# VMA.net
KiCad netlist of a schematic drawn in Altium Designer
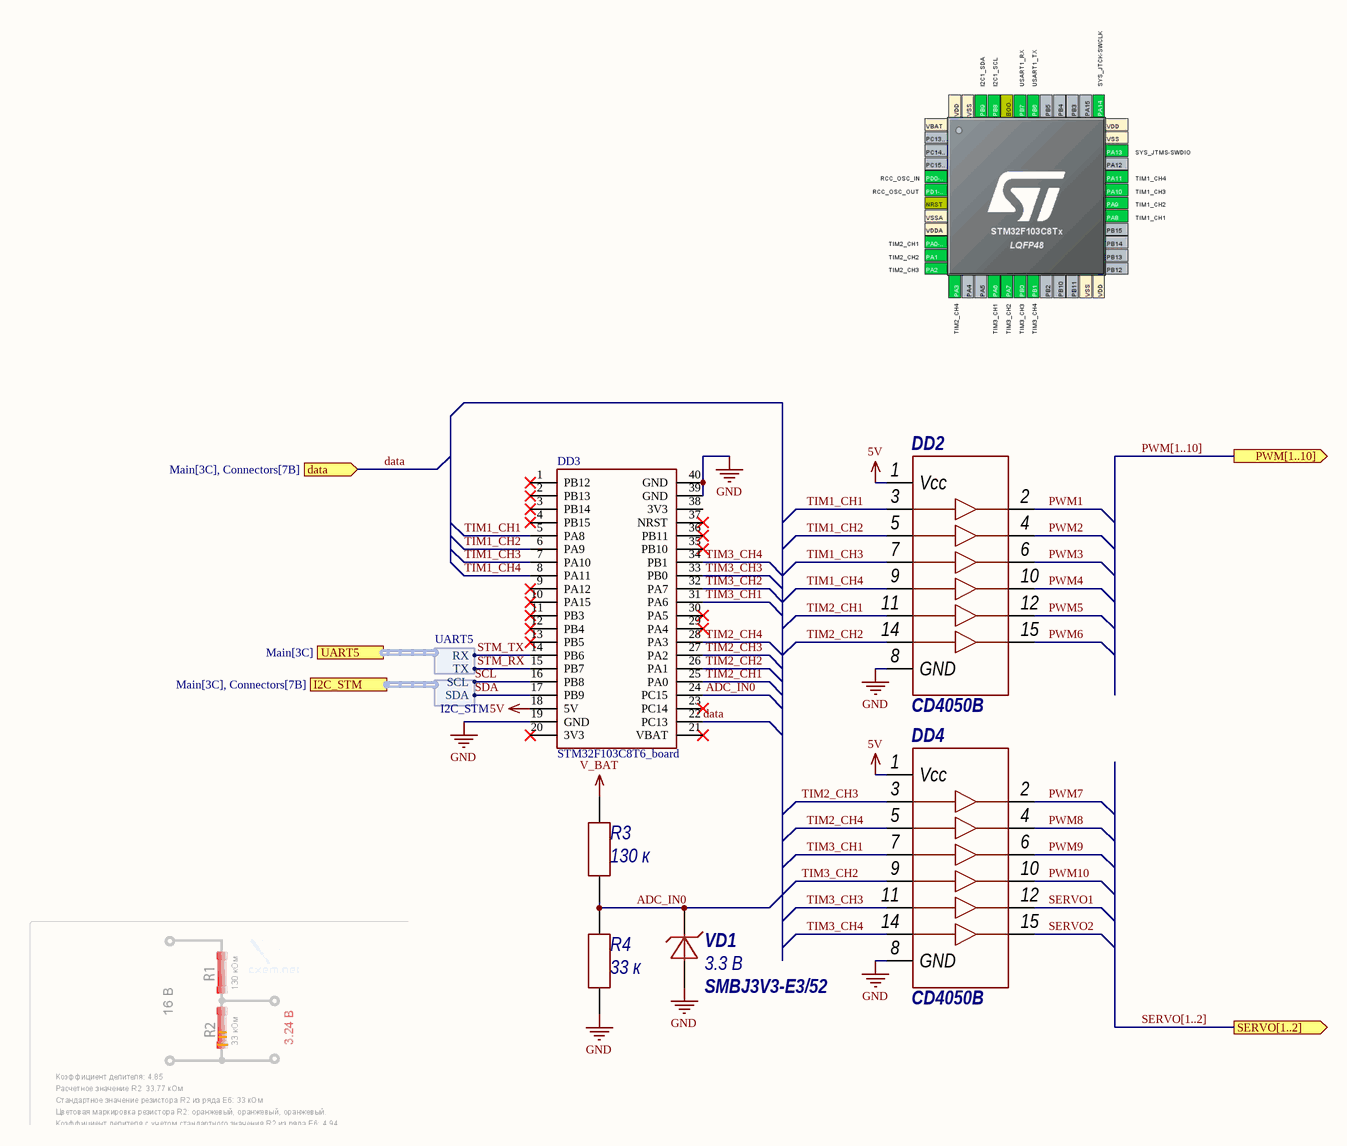
[diagram p0: VMA.SchDoc]

(export (version "E")
  (design (tool "Eeschema 10.0.6"))
  (components
    (comp (ref "DD2")
      (value "CD4050B")
      (footprint "DIP16_in_socket")
      (description "Шесть буферных элементов")
      (libsource (lib "Hydrolib") (part "CD4050B"))
    )
    (comp (ref "DD3")
      (value "STM32F103C8T6_board")
      (footprint "STM32F103C8T6_board")
      (description "blue pill")
      (libsource (lib "Hydrolib") (part "STM32F103C8T6_board"))
    )
    (comp (ref "DD4")
      (value "CD4050B")
      (footprint "DIP16_in_socket")
      (description "Шесть буферных элементов")
      (libsource (lib "Hydrolib") (part "CD4050B"))
    )
    (comp (ref "R3")
      (value "130 к")
      (footprint "0603R")
      (description "Резистор номиналом 130 кОм и точностью 1%")
      (fields (field (name "PART NUMBER") "Resistor_130k_1_0603") (field (name "TOLERANCE") "1%"))
      (libsource (lib "Hydrolib") (part "Resistor"))
    )
    (comp (ref "R4")
      (value "33 к")
      (footprint "0603R")
      (description "Резистор номиналом 33 кОм и точностью 1%")
      (fields (field (name "PART NUMBER") "Resistor_33k_1_0603") (field (name "TOLERANCE") "1%"))
      (libsource (lib "Hydrolib") (part "Resistor"))
    )
    (comp (ref "VD1")
      (value "SMBJ3V3-E3/52")
      (footprint "SMB")
      (description "Защитный диод на 15 В, рассеиваемая мощность 600 Вт")
      (fields (field (name "ALTIUM_VALUE") "3.3 В") (field (name "PART NUMBER") "SMBJ15A"))
      (libsource (lib "Hydrolib") (part "TVS_1_1dir"))
    )
  )
  (nets
    (net (code "4") (name "/ADC_IN0") (class "Default")
      (node (ref "DD3") (pin "24") (pinfunction "PC15_24") (pintype "passive"))
      (node (ref "R3") (pin "1") (pinfunction "1_1") (pintype "passive"))
      (node (ref "R4") (pin "2") (pinfunction "2_2") (pintype "passive"))
      (node (ref "VD1") (pin "2") (pinfunction "2_2") (pintype "passive"))
    )
    (net (code "5") (name "/PWM1") (class "Default")
      (node (ref "DD2") (pin "2") (pinfunction "Y1_2") (pintype "passive"))
    )
    (net (code "6") (name "/PWM2") (class "Default")
      (node (ref "DD2") (pin "4") (pinfunction "Y2_4") (pintype "passive"))
    )
    (net (code "7") (name "/PWM3") (class "Default")
      (node (ref "DD2") (pin "6") (pinfunction "Y3_6") (pintype "passive"))
    )
    (net (code "8") (name "/PWM4") (class "Default")
      (node (ref "DD2") (pin "10") (pinfunction "Y10_10") (pintype "passive"))
    )
    (net (code "9") (name "/PWM5") (class "Default")
      (node (ref "DD2") (pin "12") (pinfunction "Y5_12") (pintype "passive"))
    )
    (net (code "10") (name "/PWM6") (class "Default")
      (node (ref "DD2") (pin "15") (pinfunction "Y6_15") (pintype "passive"))
    )
    (net (code "11") (name "/PWM7") (class "Default")
      (node (ref "DD4") (pin "2") (pinfunction "Y1_2") (pintype "passive"))
    )
    (net (code "12") (name "/PWM8") (class "Default")
      (node (ref "DD4") (pin "4") (pinfunction "Y2_4") (pintype "passive"))
    )
    (net (code "13") (name "/PWM9") (class "Default")
      (node (ref "DD4") (pin "6") (pinfunction "Y3_6") (pintype "passive"))
    )
    (net (code "14") (name "/PWM10") (class "Default")
      (node (ref "DD4") (pin "10") (pinfunction "Y10_10") (pintype "passive"))
    )
    (net (code "16") (name "/SDA") (class "Default")
      (node (ref "DD3") (pin "17") (pinfunction "PB9_17") (pintype "passive"))
    )
    (net (code "17") (name "/SERVO1") (class "Default")
      (node (ref "DD4") (pin "12") (pinfunction "Y5_12") (pintype "passive"))
    )
    (net (code "18") (name "/SERVO2") (class "Default")
      (node (ref "DD4") (pin "15") (pinfunction "Y6_15") (pintype "passive"))
    )
    (net (code "20") (name "/STM_RX") (class "Default")
      (node (ref "DD3") (pin "15") (pinfunction "PB7_15") (pintype "passive"))
    )
    (net (code "21") (name "/STM_TX") (class "Default")
      (node (ref "DD3") (pin "14") (pinfunction "PB6_14") (pintype "passive"))
    )
    (net (code "22") (name "/TIM1_CH1") (class "Default")
      (node (ref "DD2") (pin "3") (pinfunction "A1_3") (pintype "passive"))
      (node (ref "DD3") (pin "5") (pinfunction "PA8_5") (pintype "passive"))
    )
    (net (code "23") (name "/TIM1_CH2") (class "Default")
      (node (ref "DD2") (pin "5") (pinfunction "A2_5") (pintype "passive"))
      (node (ref "DD3") (pin "6") (pinfunction "PA9_6") (pintype "passive"))
    )
    (net (code "24") (name "/TIM1_CH3") (class "Default")
      (node (ref "DD2") (pin "7") (pinfunction "A3_7") (pintype "passive"))
      (node (ref "DD3") (pin "7") (pinfunction "PA10_7") (pintype "passive"))
    )
    (net (code "25") (name "/TIM1_CH4") (class "Default")
      (node (ref "DD2") (pin "9") (pinfunction "A4_9") (pintype "passive"))
      (node (ref "DD3") (pin "8") (pinfunction "PA11_8") (pintype "passive"))
    )
    (net (code "26") (name "/TIM2_CH1") (class "Default")
      (node (ref "DD2") (pin "11") (pinfunction "A5_11") (pintype "passive"))
      (node (ref "DD3") (pin "25") (pinfunction "PA0_25") (pintype "passive"))
    )
    (net (code "27") (name "/TIM2_CH2") (class "Default")
      (node (ref "DD2") (pin "14") (pinfunction "A6_14") (pintype "passive"))
      (node (ref "DD3") (pin "26") (pinfunction "PA1_26") (pintype "passive"))
    )
    (net (code "28") (name "/TIM2_CH3") (class "Default")
      (node (ref "DD3") (pin "27") (pinfunction "PA2_27") (pintype "passive"))
      (node (ref "DD4") (pin "3") (pinfunction "A1_3") (pintype "passive"))
    )
    (net (code "29") (name "/TIM2_CH4") (class "Default")
      (node (ref "DD3") (pin "28") (pinfunction "PA3_28") (pintype "passive"))
      (node (ref "DD4") (pin "5") (pinfunction "A2_5") (pintype "passive"))
    )
    (net (code "30") (name "/TIM3_CH1") (class "Default")
      (node (ref "DD3") (pin "31") (pinfunction "PA6_31") (pintype "passive"))
      (node (ref "DD4") (pin "7") (pinfunction "A3_7") (pintype "passive"))
    )
    (net (code "31") (name "/TIM3_CH2") (class "Default")
      (node (ref "DD3") (pin "32") (pinfunction "PA7_32") (pintype "passive"))
      (node (ref "DD4") (pin "9") (pinfunction "A4_9") (pintype "passive"))
    )
    (net (code "32") (name "/TIM3_CH3") (class "Default")
      (node (ref "DD3") (pin "33") (pinfunction "PB0_33") (pintype "passive"))
      (node (ref "DD4") (pin "11") (pinfunction "A5_11") (pintype "passive"))
    )
    (net (code "33") (name "/TIM3_CH4") (class "Default")
      (node (ref "DD3") (pin "34") (pinfunction "PB1_34") (pintype "passive"))
      (node (ref "DD4") (pin "14") (pinfunction "A6_14") (pintype "passive"))
    )
    (net (code "35") (name "/data") (class "Default")
      (node (ref "DD3") (pin "22") (pinfunction "PC13_22") (pintype "passive"))
    )
    (net (code "37") (name "/{SCL}") (class "Default")
      (node (ref "DD3") (pin "16") (pinfunction "PB8_16") (pintype "passive"))
    )
    (net (code "38") (name "5V") (class "Default")
      (node (ref "DD2") (pin "1") (pinfunction "Vcc_1") (pintype "passive"))
      (node (ref "DD3") (pin "18") (pinfunction "5V_18") (pintype "passive"))
      (node (ref "DD4") (pin "1") (pinfunction "Vcc_1") (pintype "passive"))
    )
    (net (code "39") (name "GND") (class "Default")
      (node (ref "DD2") (pin "8") (pinfunction "GND_8") (pintype "passive"))
      (node (ref "DD3") (pin "19") (pinfunction "GND_19") (pintype "passive"))
      (node (ref "DD3") (pin "39") (pinfunction "GND_39") (pintype "passive"))
      (node (ref "DD3") (pin "40") (pinfunction "GND_40") (pintype "passive"))
      (node (ref "DD4") (pin "8") (pinfunction "GND_8") (pintype "passive"))
      (node (ref "R4") (pin "1") (pinfunction "1_1") (pintype "passive"))
      (node (ref "VD1") (pin "1") (pinfunction "1_1") (pintype "passive"))
    )
    (net (code "40") (name "V_BAT") (class "Default")
      (node (ref "R3") (pin "2") (pinfunction "2_2") (pintype "passive"))
    )
    (net (code "41") (name "unconnected-(DD3-3V3-Pad20)") (class "Default")
      (node (ref "DD3") (pin "20") (pinfunction "3V3_20") (pintype "passive+no_connect"))
    )
    (net (code "42") (name "unconnected-(DD3-3V3-Pad38)") (class "Default")
      (node (ref "DD3") (pin "38") (pinfunction "3V3_38") (pintype "passive"))
    )
    (net (code "43") (name "unconnected-(DD3-NRST-Pad37)") (class "Default")
      (node (ref "DD3") (pin "37") (pinfunction "NRST_37") (pintype "passive+no_connect"))
    )
    (net (code "44") (name "unconnected-(DD3-PA4-Pad29)") (class "Default")
      (node (ref "DD3") (pin "29") (pinfunction "PA4_29") (pintype "passive+no_connect"))
    )
    (net (code "45") (name "unconnected-(DD3-PA5-Pad30)") (class "Default")
      (node (ref "DD3") (pin "30") (pinfunction "PA5_30") (pintype "passive+no_connect"))
    )
    (net (code "46") (name "unconnected-(DD3-PA12-Pad9)") (class "Default")
      (node (ref "DD3") (pin "9") (pinfunction "PA12_9") (pintype "passive+no_connect"))
    )
    (net (code "47") (name "unconnected-(DD3-PA15-Pad10)") (class "Default")
      (node (ref "DD3") (pin "10") (pinfunction "PA15_10") (pintype "passive+no_connect"))
    )
    (net (code "48") (name "unconnected-(DD3-PB3-Pad11)") (class "Default")
      (node (ref "DD3") (pin "11") (pinfunction "PB3_11") (pintype "passive+no_connect"))
    )
    (net (code "49") (name "unconnected-(DD3-PB4-Pad12)") (class "Default")
      (node (ref "DD3") (pin "12") (pinfunction "PB4_12") (pintype "passive+no_connect"))
    )
    (net (code "50") (name "unconnected-(DD3-PB5-Pad13)") (class "Default")
      (node (ref "DD3") (pin "13") (pinfunction "PB5_13") (pintype "passive+no_connect"))
    )
    (net (code "51") (name "unconnected-(DD3-PB10-Pad35)") (class "Default")
      (node (ref "DD3") (pin "35") (pinfunction "PB10_35") (pintype "passive+no_connect"))
    )
    (net (code "52") (name "unconnected-(DD3-PB11-Pad36)") (class "Default")
      (node (ref "DD3") (pin "36") (pinfunction "PB11_36") (pintype "passive+no_connect"))
    )
    (net (code "53") (name "unconnected-(DD3-PB12-Pad1)") (class "Default")
      (node (ref "DD3") (pin "1") (pinfunction "PB12_1") (pintype "passive+no_connect"))
    )
    (net (code "54") (name "unconnected-(DD3-PB13-Pad2)") (class "Default")
      (node (ref "DD3") (pin "2") (pinfunction "PB13_2") (pintype "passive+no_connect"))
    )
    (net (code "55") (name "unconnected-(DD3-PB14-Pad3)") (class "Default")
      (node (ref "DD3") (pin "3") (pinfunction "PB14_3") (pintype "passive+no_connect"))
    )
    (net (code "56") (name "unconnected-(DD3-PB15-Pad4)") (class "Default")
      (node (ref "DD3") (pin "4") (pinfunction "PB15_4") (pintype "passive+no_connect"))
    )
    (net (code "57") (name "unconnected-(DD3-PC14-Pad23)") (class "Default")
      (node (ref "DD3") (pin "23") (pinfunction "PC14_23") (pintype "passive+no_connect"))
    )
    (net (code "58") (name "unconnected-(DD3-VBAT-Pad21)") (class "Default")
      (node (ref "DD3") (pin "21") (pinfunction "VBAT_21") (pintype "passive+no_connect"))
    )
  )
)
